# block_diagram.net
KiCad netlist of a schematic drawn in Altium Designer
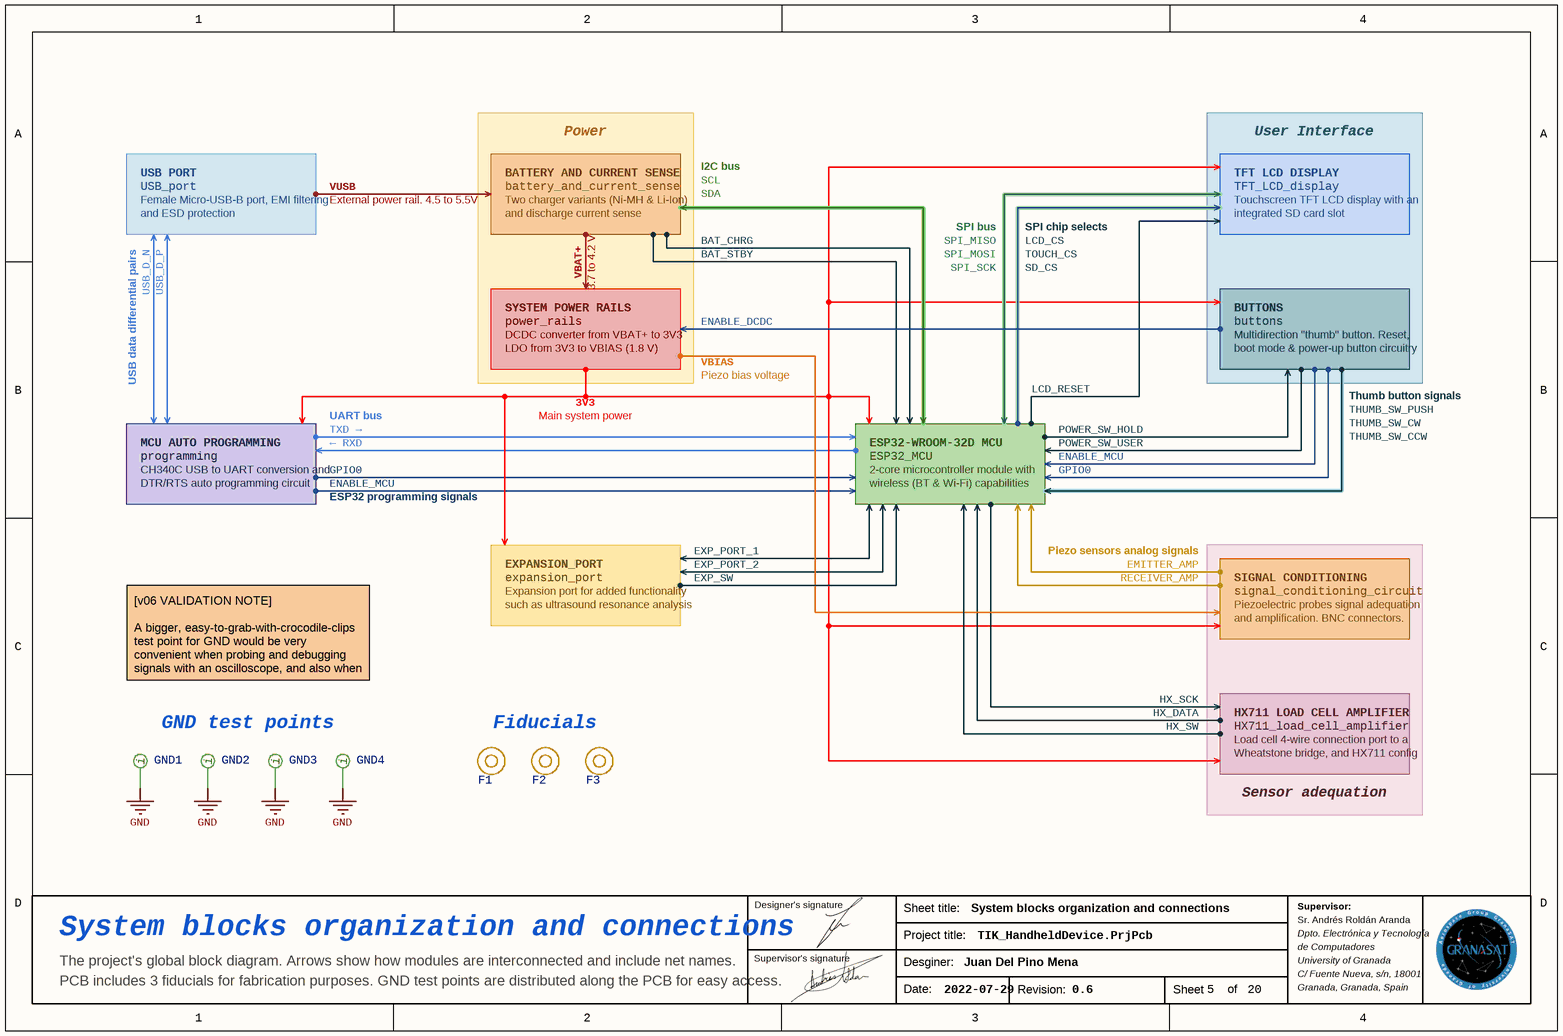
[diagram p0: block_diagram.SchDoc]

(export (version "E")
  (design (tool "Eeschema 10.0.6"))
  (components
    (comp (ref "F1")
      (value "Fiducial_1mm_2mm")
      (footprint "FIDUCIAL_1MM_2MM")
      (description "Fiducial 1mm pad, 2mm solder resist")
      (libsource (lib "tik_handheld_schlib") (part "Fiducial_1mm_2mm"))
    )
    (comp (ref "F2")
      (value "Fiducial_1mm_2mm")
      (footprint "FIDUCIAL_1MM_2MM")
      (description "Fiducial 1mm pad, 2mm solder resist")
      (libsource (lib "tik_handheld_schlib") (part "Fiducial_1mm_2mm"))
    )
    (comp (ref "F3")
      (value "Fiducial_1mm_2mm")
      (footprint "FIDUCIAL_1MM_2MM")
      (description "Fiducial 1mm pad, 2mm solder resist")
      (libsource (lib "tik_handheld_schlib") (part "Fiducial_1mm_2mm"))
    )
    (comp (ref "GND1")
      (value "Test Point Pad dual sided")
      (footprint "TEST POINT PAD")
      (description "Test point - PCB Pad dual sided")
      (libsource (lib "tik_handheld_schlib") (part "Test Point Pad dual sided"))
    )
    (comp (ref "GND2")
      (value "Test Point Pad dual sided")
      (footprint "TEST POINT PAD")
      (description "Test point - PCB Pad dual sided")
      (libsource (lib "tik_handheld_schlib") (part "Test Point Pad dual sided"))
    )
    (comp (ref "GND3")
      (value "Test Point Pad dual sided")
      (footprint "TEST POINT PAD")
      (description "Test point - PCB Pad dual sided")
      (libsource (lib "tik_handheld_schlib") (part "Test Point Pad dual sided"))
    )
    (comp (ref "GND4")
      (value "Test Point Pad dual sided")
      (footprint "TEST POINT PAD")
      (description "Test point - PCB Pad dual sided")
      (libsource (lib "tik_handheld_schlib") (part "Test Point Pad dual sided"))
    )
  )
  (nets
    (net (code "1") (name "GND") (class "Default")
      (node (ref "GND1") (pin "1") (pinfunction "1_1") (pintype "passive"))
      (node (ref "GND2") (pin "1") (pinfunction "1_1") (pintype "passive"))
      (node (ref "GND3") (pin "1") (pinfunction "1_1") (pintype "passive"))
      (node (ref "GND4") (pin "1") (pinfunction "1_1") (pintype "passive"))
    )
  )
)
